# noisesource.net
KiCad netlist of a schematic drawn in EAGLE
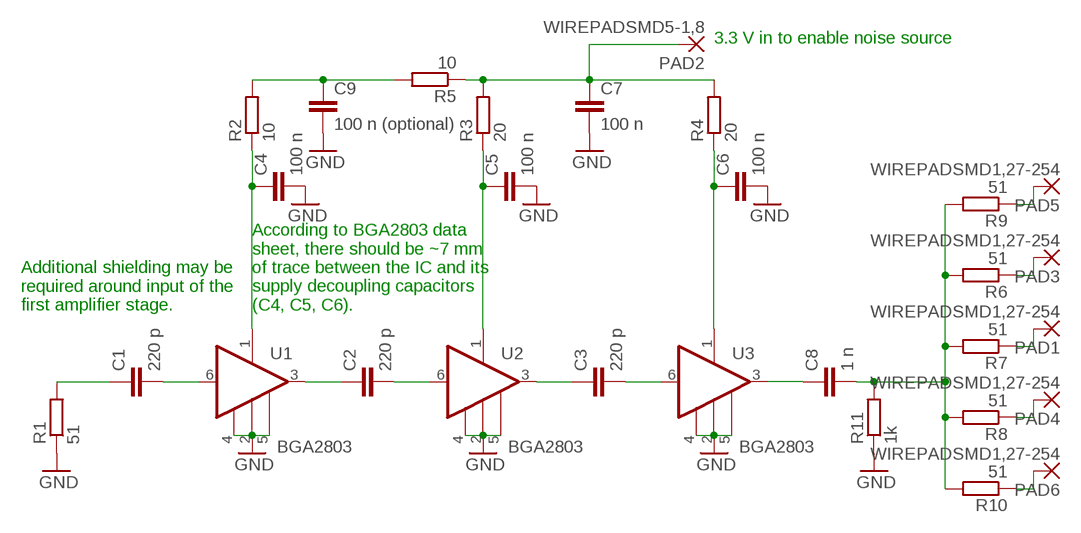
[diagram p0: schematic, sheet 1]

(export (version "E")
  (design (tool "Eeschema 10.0.6"))
  (components
    (comp (ref "C1")
      (value "220 p")
      (footprint "eagle-import:C0805")
      (libsource (lib "eagle-import") (part "C-EUC0805"))
    )
    (comp (ref "C2")
      (value "220 p")
      (footprint "eagle-import:C0805")
      (libsource (lib "eagle-import") (part "C-EUC0805"))
    )
    (comp (ref "C3")
      (value "220 p")
      (footprint "eagle-import:C0805")
      (libsource (lib "eagle-import") (part "C-EUC0805"))
    )
    (comp (ref "C4")
      (value "100 n")
      (footprint "eagle-import:C0805")
      (libsource (lib "eagle-import") (part "C-EUC0805"))
    )
    (comp (ref "C5")
      (value "100 n")
      (footprint "eagle-import:C0805")
      (libsource (lib "eagle-import") (part "C-EUC0805"))
    )
    (comp (ref "C6")
      (value "100 n")
      (footprint "eagle-import:C0805")
      (libsource (lib "eagle-import") (part "C-EUC0805"))
    )
    (comp (ref "C7")
      (value "100 n")
      (footprint "eagle-import:C0805")
      (libsource (lib "eagle-import") (part "C-EUC0805"))
    )
    (comp (ref "C8")
      (value "1 n")
      (footprint "eagle-import:C0805")
      (libsource (lib "eagle-import") (part "C-EUC0805"))
    )
    (comp (ref "C9")
      (value "100 n (optional)")
      (footprint "eagle-import:C0805")
      (libsource (lib "eagle-import") (part "C-EUC0805"))
    )
    (comp (ref "PAD1")
      (value "WIREPADSMD1,27-254")
      (footprint "eagle-import:SMD1,27-2,54")
      (libsource (lib "eagle-import") (part "WIREPADSMD1,27-254"))
    )
    (comp (ref "PAD2")
      (value "WIREPADSMD5-1,8")
      (footprint "eagle-import:5-1,8")
      (libsource (lib "eagle-import") (part "WIREPADSMD5-1,8"))
    )
    (comp (ref "PAD3")
      (value "WIREPADSMD1,27-254")
      (footprint "eagle-import:SMD1,27-2,54")
      (libsource (lib "eagle-import") (part "WIREPADSMD1,27-254"))
    )
    (comp (ref "PAD4")
      (value "WIREPADSMD1,27-254")
      (footprint "eagle-import:SMD1,27-2,54")
      (libsource (lib "eagle-import") (part "WIREPADSMD1,27-254"))
    )
    (comp (ref "PAD5")
      (value "WIREPADSMD1,27-254")
      (footprint "eagle-import:SMD1,27-2,54")
      (libsource (lib "eagle-import") (part "WIREPADSMD1,27-254"))
    )
    (comp (ref "PAD6")
      (value "WIREPADSMD1,27-254")
      (footprint "eagle-import:SMD1,27-2,54")
      (libsource (lib "eagle-import") (part "WIREPADSMD1,27-254"))
    )
    (comp (ref "R1")
      (value "51")
      (footprint "eagle-import:R0805")
      (libsource (lib "eagle-import") (part "R-EU_R0805"))
    )
    (comp (ref "R2")
      (value "10")
      (footprint "eagle-import:R0805")
      (libsource (lib "eagle-import") (part "R-EU_R0805"))
    )
    (comp (ref "R3")
      (value "20")
      (footprint "eagle-import:R0805")
      (libsource (lib "eagle-import") (part "R-EU_R0805"))
    )
    (comp (ref "R4")
      (value "20")
      (footprint "eagle-import:R0805")
      (libsource (lib "eagle-import") (part "R-EU_R0805"))
    )
    (comp (ref "R5")
      (value "10")
      (footprint "eagle-import:R0805")
      (libsource (lib "eagle-import") (part "R-EU_R0805"))
    )
    (comp (ref "R6")
      (value "51")
      (footprint "eagle-import:R0805")
      (libsource (lib "eagle-import") (part "R-EU_R0805"))
    )
    (comp (ref "R7")
      (value "51")
      (footprint "eagle-import:R0805")
      (libsource (lib "eagle-import") (part "R-EU_R0805"))
    )
    (comp (ref "R8")
      (value "51")
      (footprint "eagle-import:R0805")
      (libsource (lib "eagle-import") (part "R-EU_R0805"))
    )
    (comp (ref "R9")
      (value "51")
      (footprint "eagle-import:R0805")
      (libsource (lib "eagle-import") (part "R-EU_R0805"))
    )
    (comp (ref "R10")
      (value "51")
      (footprint "eagle-import:R0805")
      (libsource (lib "eagle-import") (part "R-EU_R0805"))
    )
    (comp (ref "R11")
      (value "1k")
      (footprint "eagle-import:R0805")
      (libsource (lib "eagle-import") (part "R-EU_R0805"))
    )
    (comp (ref "U1")
      (value "BGA2803")
      (footprint "eagle-import:SOT363")
      (libsource (lib "eagle-import") (part "BGA2850"))
    )
    (comp (ref "U2")
      (value "BGA2803")
      (footprint "eagle-import:SOT363")
      (libsource (lib "eagle-import") (part "BGA2850"))
    )
    (comp (ref "U3")
      (value "BGA2803")
      (footprint "eagle-import:SOT363")
      (libsource (lib "eagle-import") (part "BGA2850"))
    )
  )
  (nets
    (net (code "1") (name "GND") (class "Default")
      (node (ref "C4") (pin "2") (pinfunction "2_2") (pintype "passive"))
      (node (ref "C5") (pin "2") (pinfunction "2_2") (pintype "passive"))
      (node (ref "C6") (pin "2") (pinfunction "2_2") (pintype "passive"))
      (node (ref "C7") (pin "2") (pinfunction "2_2") (pintype "passive"))
      (node (ref "C9") (pin "2") (pinfunction "2_2") (pintype "passive"))
      (node (ref "R1") (pin "1") (pinfunction "1_1") (pintype "passive"))
      (node (ref "R11") (pin "1") (pinfunction "1_1") (pintype "passive"))
      (node (ref "U1") (pin "2") (pinfunction "GND2_2") (pintype "power_in"))
      (node (ref "U1") (pin "4") (pinfunction "GND1_4") (pintype "power_in"))
      (node (ref "U1") (pin "5") (pinfunction "GND2_5") (pintype "power_in"))
      (node (ref "U2") (pin "2") (pinfunction "GND2_2") (pintype "power_in"))
      (node (ref "U2") (pin "4") (pinfunction "GND1_4") (pintype "power_in"))
      (node (ref "U2") (pin "5") (pinfunction "GND2_5") (pintype "power_in"))
      (node (ref "U3") (pin "2") (pinfunction "GND2_2") (pintype "power_in"))
      (node (ref "U3") (pin "4") (pinfunction "GND1_4") (pintype "power_in"))
      (node (ref "U3") (pin "5") (pinfunction "GND2_5") (pintype "power_in"))
    )
    (net (code "2") (name "Net-(C1-Pad1)") (class "Default")
      (node (ref "C1") (pin "1") (pinfunction "1_1") (pintype "passive"))
      (node (ref "R1") (pin "2") (pinfunction "2_2") (pintype "passive"))
    )
    (net (code "3") (name "Net-(C8-Pad2)") (class "Default")
      (node (ref "C8") (pin "2") (pinfunction "2_2") (pintype "passive"))
      (node (ref "R10") (pin "2") (pinfunction "2_2") (pintype "passive"))
      (node (ref "R11") (pin "2") (pinfunction "2_2") (pintype "passive"))
      (node (ref "R6") (pin "2") (pinfunction "2_2") (pintype "passive"))
      (node (ref "R7") (pin "2") (pinfunction "2_2") (pintype "passive"))
      (node (ref "R8") (pin "2") (pinfunction "2_2") (pintype "passive"))
      (node (ref "R9") (pin "2") (pinfunction "2_2") (pintype "passive"))
    )
    (net (code "4") (name "Net-(C9-Pad1)") (class "Default")
      (node (ref "C9") (pin "1") (pinfunction "1_1") (pintype "passive"))
      (node (ref "R2") (pin "2") (pinfunction "2_2") (pintype "passive"))
      (node (ref "R5") (pin "2") (pinfunction "2_2") (pintype "passive"))
    )
    (net (code "5") (name "Net-(PAD1-P)") (class "Default")
      (node (ref "PAD1") (pin "1") (pinfunction "P_1") (pintype "passive"))
      (node (ref "R7") (pin "1") (pinfunction "1_1") (pintype "passive"))
    )
    (net (code "6") (name "Net-(PAD2-P)") (class "Default")
      (node (ref "C7") (pin "1") (pinfunction "1_1") (pintype "passive"))
      (node (ref "PAD2") (pin "1") (pinfunction "P_1") (pintype "passive"))
      (node (ref "R3") (pin "2") (pinfunction "2_2") (pintype "passive"))
      (node (ref "R4") (pin "2") (pinfunction "2_2") (pintype "passive"))
      (node (ref "R5") (pin "1") (pinfunction "1_1") (pintype "passive"))
    )
    (net (code "7") (name "Net-(PAD3-P)") (class "Default")
      (node (ref "PAD3") (pin "1") (pinfunction "P_1") (pintype "passive"))
      (node (ref "R6") (pin "1") (pinfunction "1_1") (pintype "passive"))
    )
    (net (code "8") (name "Net-(PAD4-P)") (class "Default")
      (node (ref "PAD4") (pin "1") (pinfunction "P_1") (pintype "passive"))
      (node (ref "R8") (pin "1") (pinfunction "1_1") (pintype "passive"))
    )
    (net (code "9") (name "Net-(PAD5-P)") (class "Default")
      (node (ref "PAD5") (pin "1") (pinfunction "P_1") (pintype "passive"))
      (node (ref "R9") (pin "1") (pinfunction "1_1") (pintype "passive"))
    )
    (net (code "10") (name "Net-(PAD6-P)") (class "Default")
      (node (ref "PAD6") (pin "1") (pinfunction "P_1") (pintype "passive"))
      (node (ref "R10") (pin "1") (pinfunction "1_1") (pintype "passive"))
    )
    (net (code "11") (name "Net-(U1--IN)") (class "Default")
      (node (ref "C1") (pin "2") (pinfunction "2_2") (pintype "passive"))
      (node (ref "U1") (pin "6") (pinfunction "-IN_6") (pintype "input"))
    )
    (net (code "12") (name "Net-(U1-OUT)") (class "Default")
      (node (ref "C2") (pin "1") (pinfunction "1_1") (pintype "passive"))
      (node (ref "U1") (pin "3") (pinfunction "OUT_3") (pintype "output"))
    )
    (net (code "13") (name "Net-(U1-VCC)") (class "Default")
      (node (ref "C4") (pin "1") (pinfunction "1_1") (pintype "passive"))
      (node (ref "R2") (pin "1") (pinfunction "1_1") (pintype "passive"))
      (node (ref "U1") (pin "1") (pinfunction "VCC_1") (pintype "power_in"))
    )
    (net (code "14") (name "Net-(U2--IN)") (class "Default")
      (node (ref "C2") (pin "2") (pinfunction "2_2") (pintype "passive"))
      (node (ref "U2") (pin "6") (pinfunction "-IN_6") (pintype "input"))
    )
    (net (code "15") (name "Net-(U2-OUT)") (class "Default")
      (node (ref "C3") (pin "1") (pinfunction "1_1") (pintype "passive"))
      (node (ref "U2") (pin "3") (pinfunction "OUT_3") (pintype "output"))
    )
    (net (code "16") (name "Net-(U2-VCC)") (class "Default")
      (node (ref "C5") (pin "1") (pinfunction "1_1") (pintype "passive"))
      (node (ref "R3") (pin "1") (pinfunction "1_1") (pintype "passive"))
      (node (ref "U2") (pin "1") (pinfunction "VCC_1") (pintype "power_in"))
    )
    (net (code "17") (name "Net-(U3--IN)") (class "Default")
      (node (ref "C3") (pin "2") (pinfunction "2_2") (pintype "passive"))
      (node (ref "U3") (pin "6") (pinfunction "-IN_6") (pintype "input"))
    )
    (net (code "18") (name "Net-(U3-OUT)") (class "Default")
      (node (ref "C8") (pin "1") (pinfunction "1_1") (pintype "passive"))
      (node (ref "U3") (pin "3") (pinfunction "OUT_3") (pintype "output"))
    )
    (net (code "19") (name "Net-(U3-VCC)") (class "Default")
      (node (ref "C6") (pin "1") (pinfunction "1_1") (pintype "passive"))
      (node (ref "R4") (pin "1") (pinfunction "1_1") (pintype "passive"))
      (node (ref "U3") (pin "1") (pinfunction "VCC_1") (pintype "power_in"))
    )
  )
)
